# PotDiv1_v2.net
KiCad netlist of a schematic drawn in EAGLE
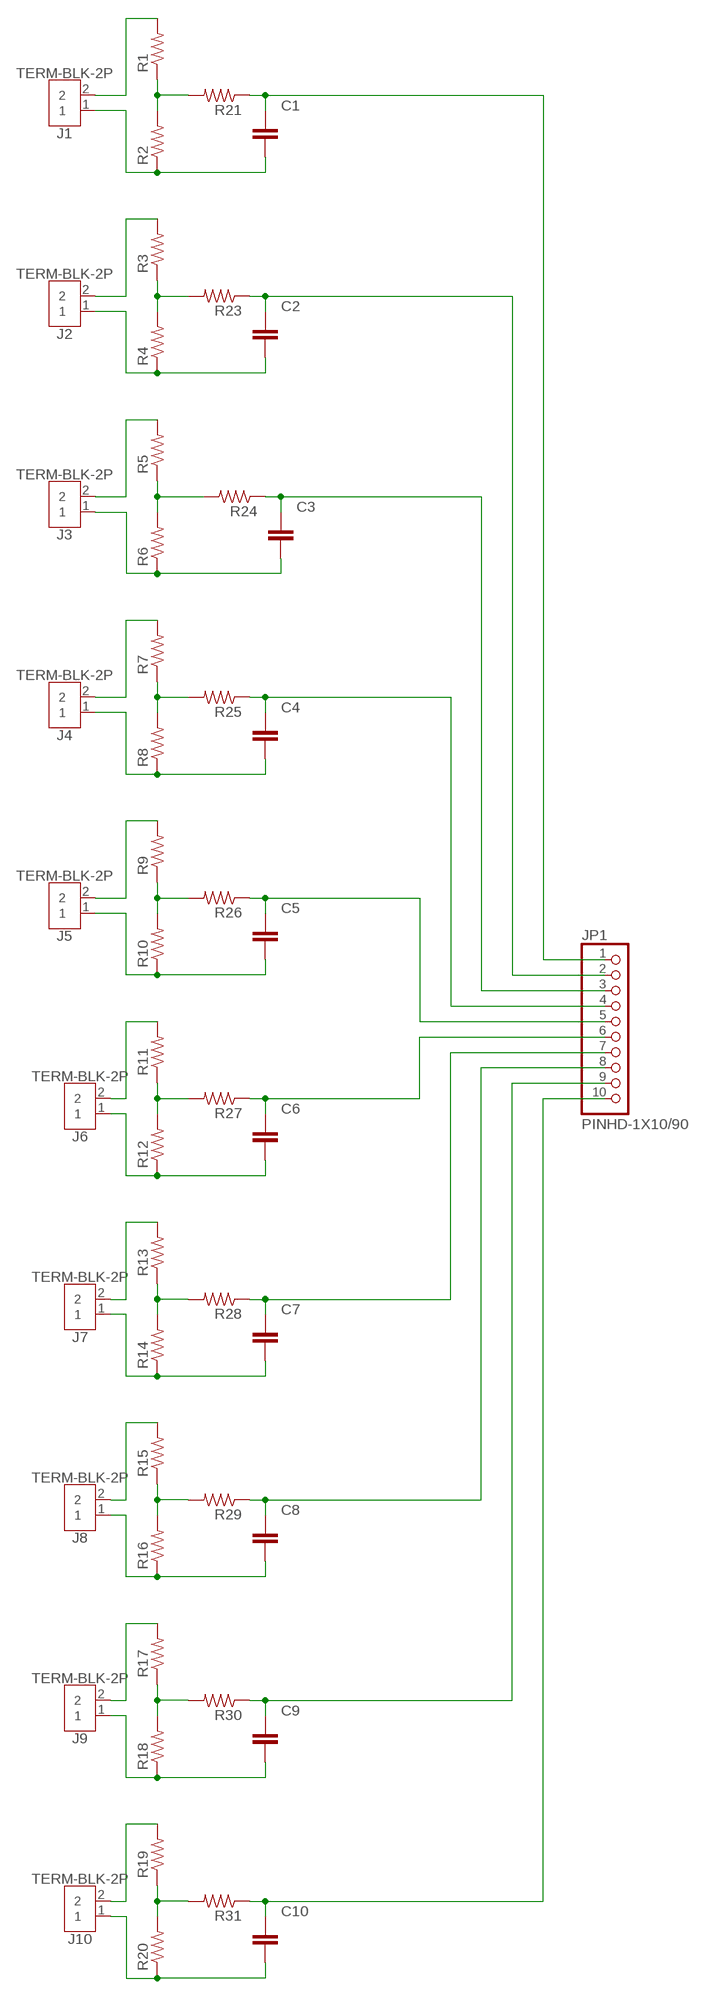
[diagram p0: schematic, sheet 1]

(export (version "E")
  (design (tool "Eeschema 10.0.6"))
  (components
    (comp (ref "C1")
      (value "C_RADIAL-12.5MM-DIA")
      (footprint "eagle-import:CAPRD550W60D1025H1250B")
      (libsource (lib "eagle-import") (part "CRADIAL-12.5MM-DIA_"))
    )
    (comp (ref "C2")
      (value "C_RADIAL-12.5MM-DIA")
      (footprint "eagle-import:CAPRD550W60D1025H1250B")
      (libsource (lib "eagle-import") (part "CRADIAL-12.5MM-DIA_"))
    )
    (comp (ref "C3")
      (value "C_RADIAL-12.5MM-DIA")
      (footprint "eagle-import:CAPRD550W60D1025H1250B")
      (libsource (lib "eagle-import") (part "CRADIAL-12.5MM-DIA_"))
    )
    (comp (ref "C4")
      (value "C_RADIAL-12.5MM-DIA")
      (footprint "eagle-import:CAPRD550W60D1025H1250B")
      (libsource (lib "eagle-import") (part "CRADIAL-12.5MM-DIA_"))
    )
    (comp (ref "C5")
      (value "C_RADIAL-12.5MM-DIA")
      (footprint "eagle-import:CAPRD550W60D1025H1250B")
      (libsource (lib "eagle-import") (part "CRADIAL-12.5MM-DIA_"))
    )
    (comp (ref "C6")
      (value "C_RADIAL-12.5MM-DIA")
      (footprint "eagle-import:CAPRD550W60D1025H1250B")
      (libsource (lib "eagle-import") (part "CRADIAL-12.5MM-DIA_"))
    )
    (comp (ref "C7")
      (value "C_RADIAL-12.5MM-DIA")
      (footprint "eagle-import:CAPRD550W60D1025H1250B")
      (libsource (lib "eagle-import") (part "CRADIAL-12.5MM-DIA_"))
    )
    (comp (ref "C8")
      (value "C_RADIAL-12.5MM-DIA")
      (footprint "eagle-import:CAPRD550W60D1025H1250B")
      (libsource (lib "eagle-import") (part "CRADIAL-12.5MM-DIA_"))
    )
    (comp (ref "C9")
      (value "C_RADIAL-12.5MM-DIA")
      (footprint "eagle-import:CAPRD550W60D1025H1250B")
      (libsource (lib "eagle-import") (part "CRADIAL-12.5MM-DIA_"))
    )
    (comp (ref "C10")
      (value "C_RADIAL-12.5MM-DIA")
      (footprint "eagle-import:CAPRD550W60D1025H1250B")
      (libsource (lib "eagle-import") (part "CRADIAL-12.5MM-DIA_"))
    )
    (comp (ref "J1")
      (value "TERM-BLK-2P")
      (footprint "eagle-import:TERMBLK_508-2N")
      (fields (field (name "MANUFACTURER") "TE Connectivity AMP Connectors") (field (name "MPN") "282837-2"))
      (libsource (lib "eagle-import") (part "2828XX-2282837-2"))
    )
    (comp (ref "J2")
      (value "TERM-BLK-2P")
      (footprint "eagle-import:TERMBLK_508-2N")
      (fields (field (name "MANUFACTURER") "TE Connectivity AMP Connectors") (field (name "MPN") "282837-2"))
      (libsource (lib "eagle-import") (part "2828XX-2282837-2"))
    )
    (comp (ref "J3")
      (value "TERM-BLK-2P")
      (footprint "eagle-import:TERMBLK_508-2N")
      (fields (field (name "MANUFACTURER") "TE Connectivity AMP Connectors") (field (name "MPN") "282837-2"))
      (libsource (lib "eagle-import") (part "2828XX-2282837-2"))
    )
    (comp (ref "J4")
      (value "TERM-BLK-2P")
      (footprint "eagle-import:TERMBLK_508-2N")
      (fields (field (name "MANUFACTURER") "TE Connectivity AMP Connectors") (field (name "MPN") "282837-2"))
      (libsource (lib "eagle-import") (part "2828XX-2282837-2"))
    )
    (comp (ref "J5")
      (value "TERM-BLK-2P")
      (footprint "eagle-import:TERMBLK_508-2N")
      (fields (field (name "MANUFACTURER") "TE Connectivity AMP Connectors") (field (name "MPN") "282837-2"))
      (libsource (lib "eagle-import") (part "2828XX-2282837-2"))
    )
    (comp (ref "J6")
      (value "TERM-BLK-2P")
      (footprint "eagle-import:TERMBLK_508-2N")
      (fields (field (name "MANUFACTURER") "TE Connectivity AMP Connectors") (field (name "MPN") "282837-2"))
      (libsource (lib "eagle-import") (part "2828XX-2282837-2"))
    )
    (comp (ref "J7")
      (value "TERM-BLK-2P")
      (footprint "eagle-import:TERMBLK_508-2N")
      (fields (field (name "MANUFACTURER") "TE Connectivity AMP Connectors") (field (name "MPN") "282837-2"))
      (libsource (lib "eagle-import") (part "2828XX-2282837-2"))
    )
    (comp (ref "J8")
      (value "TERM-BLK-2P")
      (footprint "eagle-import:TERMBLK_508-2N")
      (fields (field (name "MANUFACTURER") "TE Connectivity AMP Connectors") (field (name "MPN") "282837-2"))
      (libsource (lib "eagle-import") (part "2828XX-2282837-2"))
    )
    (comp (ref "J9")
      (value "TERM-BLK-2P")
      (footprint "eagle-import:TERMBLK_508-2N")
      (fields (field (name "MANUFACTURER") "TE Connectivity AMP Connectors") (field (name "MPN") "282837-2"))
      (libsource (lib "eagle-import") (part "2828XX-2282837-2"))
    )
    (comp (ref "J10")
      (value "TERM-BLK-2P")
      (footprint "eagle-import:TERMBLK_508-2N")
      (fields (field (name "MANUFACTURER") "TE Connectivity AMP Connectors") (field (name "MPN") "282837-2"))
      (libsource (lib "eagle-import") (part "2828XX-2282837-2"))
    )
    (comp (ref "JP1")
      (value "PINHD-1X10/90")
      (footprint "eagle-import:1X10_90")
      (fields (field (name "MANUFACTURER") "Generic"))
      (libsource (lib "eagle-import") (part "PINHD-1X10/90"))
    )
    (comp (ref "R1")
      (value "R-US_AXIAL-7.2MM-PITCH")
      (footprint "eagle-import:RESAD724W46L381D178B")
      (libsource (lib "eagle-import") (part "R-USAXIAL-7.2MM-PITCH_"))
    )
    (comp (ref "R2")
      (value "R-US_AXIAL-7.2MM-PITCH")
      (footprint "eagle-import:RESAD724W46L381D178B")
      (libsource (lib "eagle-import") (part "R-USAXIAL-7.2MM-PITCH_"))
    )
    (comp (ref "R3")
      (value "R-US_AXIAL-7.2MM-PITCH")
      (footprint "eagle-import:RESAD724W46L381D178B")
      (libsource (lib "eagle-import") (part "R-USAXIAL-7.2MM-PITCH_"))
    )
    (comp (ref "R4")
      (value "R-US_AXIAL-7.2MM-PITCH")
      (footprint "eagle-import:RESAD724W46L381D178B")
      (libsource (lib "eagle-import") (part "R-USAXIAL-7.2MM-PITCH_"))
    )
    (comp (ref "R5")
      (value "R-US_AXIAL-7.2MM-PITCH")
      (footprint "eagle-import:RESAD724W46L381D178B")
      (libsource (lib "eagle-import") (part "R-USAXIAL-7.2MM-PITCH_"))
    )
    (comp (ref "R6")
      (value "R-US_AXIAL-7.2MM-PITCH")
      (footprint "eagle-import:RESAD724W46L381D178B")
      (libsource (lib "eagle-import") (part "R-USAXIAL-7.2MM-PITCH_"))
    )
    (comp (ref "R7")
      (value "R-US_AXIAL-7.2MM-PITCH")
      (footprint "eagle-import:RESAD724W46L381D178B")
      (libsource (lib "eagle-import") (part "R-USAXIAL-7.2MM-PITCH_"))
    )
    (comp (ref "R8")
      (value "R-US_AXIAL-7.2MM-PITCH")
      (footprint "eagle-import:RESAD724W46L381D178B")
      (libsource (lib "eagle-import") (part "R-USAXIAL-7.2MM-PITCH_"))
    )
    (comp (ref "R9")
      (value "R-US_AXIAL-7.2MM-PITCH")
      (footprint "eagle-import:RESAD724W46L381D178B")
      (libsource (lib "eagle-import") (part "R-USAXIAL-7.2MM-PITCH_"))
    )
    (comp (ref "R10")
      (value "R-US_AXIAL-7.2MM-PITCH")
      (footprint "eagle-import:RESAD724W46L381D178B")
      (libsource (lib "eagle-import") (part "R-USAXIAL-7.2MM-PITCH_"))
    )
    (comp (ref "R11")
      (value "R-US_AXIAL-7.2MM-PITCH")
      (footprint "eagle-import:RESAD724W46L381D178B")
      (libsource (lib "eagle-import") (part "R-USAXIAL-7.2MM-PITCH_"))
    )
    (comp (ref "R12")
      (value "R-US_AXIAL-7.2MM-PITCH")
      (footprint "eagle-import:RESAD724W46L381D178B")
      (libsource (lib "eagle-import") (part "R-USAXIAL-7.2MM-PITCH_"))
    )
    (comp (ref "R13")
      (value "R-US_AXIAL-7.2MM-PITCH")
      (footprint "eagle-import:RESAD724W46L381D178B")
      (libsource (lib "eagle-import") (part "R-USAXIAL-7.2MM-PITCH_"))
    )
    (comp (ref "R14")
      (value "R-US_AXIAL-7.2MM-PITCH")
      (footprint "eagle-import:RESAD724W46L381D178B")
      (libsource (lib "eagle-import") (part "R-USAXIAL-7.2MM-PITCH_"))
    )
    (comp (ref "R15")
      (value "R-US_AXIAL-7.2MM-PITCH")
      (footprint "eagle-import:RESAD724W46L381D178B")
      (libsource (lib "eagle-import") (part "R-USAXIAL-7.2MM-PITCH_"))
    )
    (comp (ref "R16")
      (value "R-US_AXIAL-7.2MM-PITCH")
      (footprint "eagle-import:RESAD724W46L381D178B")
      (libsource (lib "eagle-import") (part "R-USAXIAL-7.2MM-PITCH_"))
    )
    (comp (ref "R17")
      (value "R-US_AXIAL-7.2MM-PITCH")
      (footprint "eagle-import:RESAD724W46L381D178B")
      (libsource (lib "eagle-import") (part "R-USAXIAL-7.2MM-PITCH_"))
    )
    (comp (ref "R18")
      (value "R-US_AXIAL-7.2MM-PITCH")
      (footprint "eagle-import:RESAD724W46L381D178B")
      (libsource (lib "eagle-import") (part "R-USAXIAL-7.2MM-PITCH_"))
    )
    (comp (ref "R19")
      (value "R-US_AXIAL-7.2MM-PITCH")
      (footprint "eagle-import:RESAD724W46L381D178B")
      (libsource (lib "eagle-import") (part "R-USAXIAL-7.2MM-PITCH_"))
    )
    (comp (ref "R20")
      (value "R-US_AXIAL-7.2MM-PITCH")
      (footprint "eagle-import:RESAD724W46L381D178B")
      (libsource (lib "eagle-import") (part "R-USAXIAL-7.2MM-PITCH_"))
    )
    (comp (ref "R21")
      (value "R-US_AXIAL-7.2MM-PITCH")
      (footprint "eagle-import:RESAD724W46L381D178B")
      (libsource (lib "eagle-import") (part "R-USAXIAL-7.2MM-PITCH_"))
    )
    (comp (ref "R23")
      (value "R-US_AXIAL-7.2MM-PITCH")
      (footprint "eagle-import:RESAD724W46L381D178B")
      (libsource (lib "eagle-import") (part "R-USAXIAL-7.2MM-PITCH_"))
    )
    (comp (ref "R24")
      (value "R-US_AXIAL-7.2MM-PITCH")
      (footprint "eagle-import:RESAD724W46L381D178B")
      (libsource (lib "eagle-import") (part "R-USAXIAL-7.2MM-PITCH_"))
    )
    (comp (ref "R25")
      (value "R-US_AXIAL-7.2MM-PITCH")
      (footprint "eagle-import:RESAD724W46L381D178B")
      (libsource (lib "eagle-import") (part "R-USAXIAL-7.2MM-PITCH_"))
    )
    (comp (ref "R26")
      (value "R-US_AXIAL-7.2MM-PITCH")
      (footprint "eagle-import:RESAD724W46L381D178B")
      (libsource (lib "eagle-import") (part "R-USAXIAL-7.2MM-PITCH_"))
    )
    (comp (ref "R27")
      (value "R-US_AXIAL-7.2MM-PITCH")
      (footprint "eagle-import:RESAD724W46L381D178B")
      (libsource (lib "eagle-import") (part "R-USAXIAL-7.2MM-PITCH_"))
    )
    (comp (ref "R28")
      (value "R-US_AXIAL-7.2MM-PITCH")
      (footprint "eagle-import:RESAD724W46L381D178B")
      (libsource (lib "eagle-import") (part "R-USAXIAL-7.2MM-PITCH_"))
    )
    (comp (ref "R29")
      (value "R-US_AXIAL-7.2MM-PITCH")
      (footprint "eagle-import:RESAD724W46L381D178B")
      (libsource (lib "eagle-import") (part "R-USAXIAL-7.2MM-PITCH_"))
    )
    (comp (ref "R30")
      (value "R-US_AXIAL-7.2MM-PITCH")
      (footprint "eagle-import:RESAD724W46L381D178B")
      (libsource (lib "eagle-import") (part "R-USAXIAL-7.2MM-PITCH_"))
    )
    (comp (ref "R31")
      (value "R-US_AXIAL-7.2MM-PITCH")
      (footprint "eagle-import:RESAD724W46L381D178B")
      (libsource (lib "eagle-import") (part "R-USAXIAL-7.2MM-PITCH_"))
    )
  )
  (nets
    (net (code "1") (name "Net-(C1-Pad1)") (class "Default")
      (node (ref "C1") (pin "1") (pinfunction "1_1") (pintype "passive"))
      (node (ref "JP1") (pin "1") (pinfunction "1_1") (pintype "passive"))
      (node (ref "R21") (pin "1") (pinfunction "1_1") (pintype "passive"))
    )
    (net (code "2") (name "Net-(C1-Pad2)") (class "Default")
      (node (ref "C1") (pin "2") (pinfunction "2_2") (pintype "passive"))
      (node (ref "J1") (pin "1") (pinfunction "1_1") (pintype "bidirectional"))
      (node (ref "R2") (pin "1") (pinfunction "1_1") (pintype "passive"))
    )
    (net (code "3") (name "Net-(C2-Pad1)") (class "Default")
      (node (ref "C2") (pin "1") (pinfunction "1_1") (pintype "passive"))
      (node (ref "JP1") (pin "2") (pinfunction "2_2") (pintype "passive"))
      (node (ref "R23") (pin "1") (pinfunction "1_1") (pintype "passive"))
    )
    (net (code "4") (name "Net-(C2-Pad2)") (class "Default")
      (node (ref "C2") (pin "2") (pinfunction "2_2") (pintype "passive"))
      (node (ref "J2") (pin "1") (pinfunction "1_1") (pintype "bidirectional"))
      (node (ref "R4") (pin "1") (pinfunction "1_1") (pintype "passive"))
    )
    (net (code "5") (name "Net-(C3-Pad1)") (class "Default")
      (node (ref "C3") (pin "1") (pinfunction "1_1") (pintype "passive"))
      (node (ref "JP1") (pin "3") (pinfunction "3_3") (pintype "passive"))
      (node (ref "R24") (pin "1") (pinfunction "1_1") (pintype "passive"))
    )
    (net (code "6") (name "Net-(C3-Pad2)") (class "Default")
      (node (ref "C3") (pin "2") (pinfunction "2_2") (pintype "passive"))
      (node (ref "J3") (pin "1") (pinfunction "1_1") (pintype "bidirectional"))
      (node (ref "R6") (pin "1") (pinfunction "1_1") (pintype "passive"))
    )
    (net (code "7") (name "Net-(C4-Pad1)") (class "Default")
      (node (ref "C4") (pin "1") (pinfunction "1_1") (pintype "passive"))
      (node (ref "JP1") (pin "4") (pinfunction "4_4") (pintype "passive"))
      (node (ref "R25") (pin "1") (pinfunction "1_1") (pintype "passive"))
    )
    (net (code "8") (name "Net-(C4-Pad2)") (class "Default")
      (node (ref "C4") (pin "2") (pinfunction "2_2") (pintype "passive"))
      (node (ref "J4") (pin "1") (pinfunction "1_1") (pintype "bidirectional"))
      (node (ref "R8") (pin "1") (pinfunction "1_1") (pintype "passive"))
    )
    (net (code "9") (name "Net-(C5-Pad1)") (class "Default")
      (node (ref "C5") (pin "1") (pinfunction "1_1") (pintype "passive"))
      (node (ref "JP1") (pin "5") (pinfunction "5_5") (pintype "passive"))
      (node (ref "R26") (pin "1") (pinfunction "1_1") (pintype "passive"))
    )
    (net (code "10") (name "Net-(C5-Pad2)") (class "Default")
      (node (ref "C5") (pin "2") (pinfunction "2_2") (pintype "passive"))
      (node (ref "J5") (pin "1") (pinfunction "1_1") (pintype "bidirectional"))
      (node (ref "R10") (pin "1") (pinfunction "1_1") (pintype "passive"))
    )
    (net (code "11") (name "Net-(C6-Pad1)") (class "Default")
      (node (ref "C6") (pin "1") (pinfunction "1_1") (pintype "passive"))
      (node (ref "JP1") (pin "6") (pinfunction "6_6") (pintype "passive"))
      (node (ref "R27") (pin "1") (pinfunction "1_1") (pintype "passive"))
    )
    (net (code "12") (name "Net-(C6-Pad2)") (class "Default")
      (node (ref "C6") (pin "2") (pinfunction "2_2") (pintype "passive"))
      (node (ref "J6") (pin "1") (pinfunction "1_1") (pintype "bidirectional"))
      (node (ref "R12") (pin "1") (pinfunction "1_1") (pintype "passive"))
    )
    (net (code "13") (name "Net-(C7-Pad1)") (class "Default")
      (node (ref "C7") (pin "1") (pinfunction "1_1") (pintype "passive"))
      (node (ref "JP1") (pin "7") (pinfunction "7_7") (pintype "passive"))
      (node (ref "R28") (pin "1") (pinfunction "1_1") (pintype "passive"))
    )
    (net (code "14") (name "Net-(C7-Pad2)") (class "Default")
      (node (ref "C7") (pin "2") (pinfunction "2_2") (pintype "passive"))
      (node (ref "J7") (pin "1") (pinfunction "1_1") (pintype "bidirectional"))
      (node (ref "R14") (pin "1") (pinfunction "1_1") (pintype "passive"))
    )
    (net (code "15") (name "Net-(C8-Pad1)") (class "Default")
      (node (ref "C8") (pin "1") (pinfunction "1_1") (pintype "passive"))
      (node (ref "JP1") (pin "8") (pinfunction "8_8") (pintype "passive"))
      (node (ref "R29") (pin "1") (pinfunction "1_1") (pintype "passive"))
    )
    (net (code "16") (name "Net-(C8-Pad2)") (class "Default")
      (node (ref "C8") (pin "2") (pinfunction "2_2") (pintype "passive"))
      (node (ref "J8") (pin "1") (pinfunction "1_1") (pintype "bidirectional"))
      (node (ref "R16") (pin "1") (pinfunction "1_1") (pintype "passive"))
    )
    (net (code "17") (name "Net-(C9-Pad1)") (class "Default")
      (node (ref "C9") (pin "1") (pinfunction "1_1") (pintype "passive"))
      (node (ref "JP1") (pin "9") (pinfunction "9_9") (pintype "passive"))
      (node (ref "R30") (pin "1") (pinfunction "1_1") (pintype "passive"))
    )
    (net (code "18") (name "Net-(C9-Pad2)") (class "Default")
      (node (ref "C9") (pin "2") (pinfunction "2_2") (pintype "passive"))
      (node (ref "J9") (pin "1") (pinfunction "1_1") (pintype "bidirectional"))
      (node (ref "R18") (pin "1") (pinfunction "1_1") (pintype "passive"))
    )
    (net (code "19") (name "Net-(C10-Pad1)") (class "Default")
      (node (ref "C10") (pin "1") (pinfunction "1_1") (pintype "passive"))
      (node (ref "JP1") (pin "10") (pinfunction "10_10") (pintype "passive"))
      (node (ref "R31") (pin "1") (pinfunction "1_1") (pintype "passive"))
    )
    (net (code "20") (name "Net-(C10-Pad2)") (class "Default")
      (node (ref "C10") (pin "2") (pinfunction "2_2") (pintype "passive"))
      (node (ref "J10") (pin "1") (pinfunction "1_1") (pintype "bidirectional"))
      (node (ref "R20") (pin "1") (pinfunction "1_1") (pintype "passive"))
    )
    (net (code "21") (name "Net-(J1-Pad2)") (class "Default")
      (node (ref "J1") (pin "2") (pinfunction "2_2") (pintype "bidirectional"))
      (node (ref "R1") (pin "2") (pinfunction "2_2") (pintype "passive"))
    )
    (net (code "22") (name "Net-(J2-Pad2)") (class "Default")
      (node (ref "J2") (pin "2") (pinfunction "2_2") (pintype "bidirectional"))
      (node (ref "R3") (pin "2") (pinfunction "2_2") (pintype "passive"))
    )
    (net (code "23") (name "Net-(J3-Pad2)") (class "Default")
      (node (ref "J3") (pin "2") (pinfunction "2_2") (pintype "bidirectional"))
      (node (ref "R5") (pin "2") (pinfunction "2_2") (pintype "passive"))
    )
    (net (code "24") (name "Net-(J4-Pad2)") (class "Default")
      (node (ref "J4") (pin "2") (pinfunction "2_2") (pintype "bidirectional"))
      (node (ref "R7") (pin "2") (pinfunction "2_2") (pintype "passive"))
    )
    (net (code "25") (name "Net-(J5-Pad2)") (class "Default")
      (node (ref "J5") (pin "2") (pinfunction "2_2") (pintype "bidirectional"))
      (node (ref "R9") (pin "2") (pinfunction "2_2") (pintype "passive"))
    )
    (net (code "26") (name "Net-(J6-Pad2)") (class "Default")
      (node (ref "J6") (pin "2") (pinfunction "2_2") (pintype "bidirectional"))
      (node (ref "R11") (pin "2") (pinfunction "2_2") (pintype "passive"))
    )
    (net (code "27") (name "Net-(J7-Pad2)") (class "Default")
      (node (ref "J7") (pin "2") (pinfunction "2_2") (pintype "bidirectional"))
      (node (ref "R13") (pin "2") (pinfunction "2_2") (pintype "passive"))
    )
    (net (code "28") (name "Net-(J8-Pad2)") (class "Default")
      (node (ref "J8") (pin "2") (pinfunction "2_2") (pintype "bidirectional"))
      (node (ref "R15") (pin "2") (pinfunction "2_2") (pintype "passive"))
    )
    (net (code "29") (name "Net-(J9-Pad2)") (class "Default")
      (node (ref "J9") (pin "2") (pinfunction "2_2") (pintype "bidirectional"))
      (node (ref "R17") (pin "2") (pinfunction "2_2") (pintype "passive"))
    )
    (net (code "30") (name "Net-(J10-Pad2)") (class "Default")
      (node (ref "J10") (pin "2") (pinfunction "2_2") (pintype "bidirectional"))
      (node (ref "R19") (pin "2") (pinfunction "2_2") (pintype "passive"))
    )
    (net (code "31") (name "Net-(R1-Pad1)") (class "Default")
      (node (ref "R1") (pin "1") (pinfunction "1_1") (pintype "passive"))
      (node (ref "R2") (pin "2") (pinfunction "2_2") (pintype "passive"))
      (node (ref "R21") (pin "2") (pinfunction "2_2") (pintype "passive"))
    )
    (net (code "32") (name "Net-(R10-Pad2)") (class "Default")
      (node (ref "R10") (pin "2") (pinfunction "2_2") (pintype "passive"))
      (node (ref "R26") (pin "2") (pinfunction "2_2") (pintype "passive"))
      (node (ref "R9") (pin "1") (pinfunction "1_1") (pintype "passive"))
    )
    (net (code "33") (name "Net-(R11-Pad1)") (class "Default")
      (node (ref "R11") (pin "1") (pinfunction "1_1") (pintype "passive"))
      (node (ref "R12") (pin "2") (pinfunction "2_2") (pintype "passive"))
      (node (ref "R27") (pin "2") (pinfunction "2_2") (pintype "passive"))
    )
    (net (code "34") (name "Net-(R13-Pad1)") (class "Default")
      (node (ref "R13") (pin "1") (pinfunction "1_1") (pintype "passive"))
      (node (ref "R14") (pin "2") (pinfunction "2_2") (pintype "passive"))
      (node (ref "R28") (pin "2") (pinfunction "2_2") (pintype "passive"))
    )
    (net (code "35") (name "Net-(R15-Pad1)") (class "Default")
      (node (ref "R15") (pin "1") (pinfunction "1_1") (pintype "passive"))
      (node (ref "R16") (pin "2") (pinfunction "2_2") (pintype "passive"))
      (node (ref "R29") (pin "2") (pinfunction "2_2") (pintype "passive"))
    )
    (net (code "36") (name "Net-(R17-Pad1)") (class "Default")
      (node (ref "R17") (pin "1") (pinfunction "1_1") (pintype "passive"))
      (node (ref "R18") (pin "2") (pinfunction "2_2") (pintype "passive"))
      (node (ref "R30") (pin "2") (pinfunction "2_2") (pintype "passive"))
    )
    (net (code "37") (name "Net-(R19-Pad1)") (class "Default")
      (node (ref "R19") (pin "1") (pinfunction "1_1") (pintype "passive"))
      (node (ref "R20") (pin "2") (pinfunction "2_2") (pintype "passive"))
      (node (ref "R31") (pin "2") (pinfunction "2_2") (pintype "passive"))
    )
    (net (code "38") (name "Net-(R23-Pad2)") (class "Default")
      (node (ref "R23") (pin "2") (pinfunction "2_2") (pintype "passive"))
      (node (ref "R3") (pin "1") (pinfunction "1_1") (pintype "passive"))
      (node (ref "R4") (pin "2") (pinfunction "2_2") (pintype "passive"))
    )
    (net (code "39") (name "Net-(R24-Pad2)") (class "Default")
      (node (ref "R24") (pin "2") (pinfunction "2_2") (pintype "passive"))
      (node (ref "R5") (pin "1") (pinfunction "1_1") (pintype "passive"))
      (node (ref "R6") (pin "2") (pinfunction "2_2") (pintype "passive"))
    )
    (net (code "40") (name "Net-(R25-Pad2)") (class "Default")
      (node (ref "R25") (pin "2") (pinfunction "2_2") (pintype "passive"))
      (node (ref "R7") (pin "1") (pinfunction "1_1") (pintype "passive"))
      (node (ref "R8") (pin "2") (pinfunction "2_2") (pintype "passive"))
    )
  )
)
